# SCH_SPEAKER.net
KiCad netlist of a schematic drawn in Altium Designer
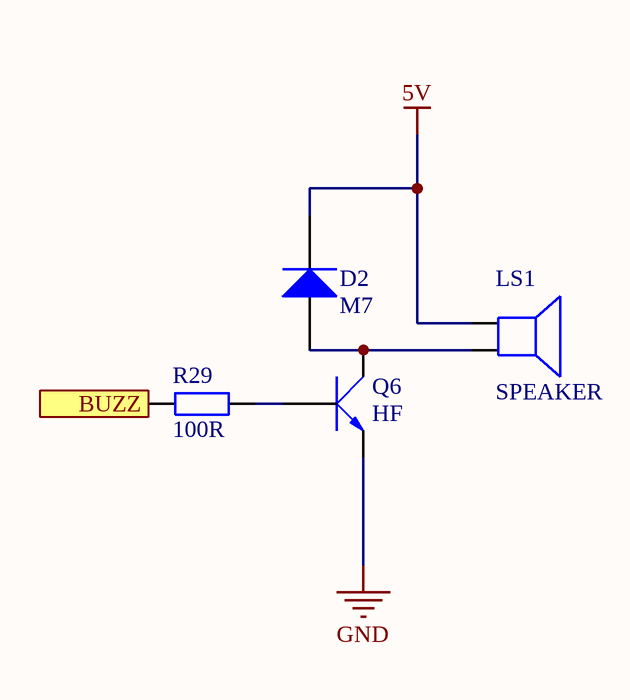
[diagram p0: SCH_SPEAKER.SchDoc]

(export (version "E")
  (design (tool "Eeschema 10.0.6"))
  (components
    (comp (ref "D2")
      (value "M7")
      (footprint "DIODE SMA")
      (description "Dán")
      (libsource (lib "Altium_Lib_by_KhueNguyenCreator") (part "Diode M7 ( 4007 )"))
    )
    (comp (ref "LS1")
      (value "SPEAKER")
      (footprint "Coi Chip Speacker")
      (description "Còi chip")
      (libsource (lib "Altium_Lib_by_KhueNguyenCreator") (part "Coi Chip Speaker"))
    )
    (comp (ref "Q6")
      (value "HF")
      (footprint "SOT23")
      (description "NPN transistor")
      (libsource (lib "Altium_Lib_by_KhueNguyenCreator") (part "C1815 HF SMD"))
    )
    (comp (ref "R29")
      (value "100R")
      (footprint "tro smd 0805")
      (description "Dán")
      (libsource (lib "Altium_Lib_by_KhueNguyenCreator") (part "Tro 0805 5% 100R"))
    )
  )
  (nets
    (net (code "2") (name "/BUZZ") (class "Default")
      (node (ref "R29") (pin "1") (pinfunction "1_1") (pintype "passive"))
    )
    (net (code "3") (name "5V") (class "Default")
      (node (ref "D2") (pin "2") (pinfunction "K_2") (pintype "passive"))
      (node (ref "LS1") (pin "1") (pinfunction "1_1") (pintype "passive"))
    )
    (net (code "4") (name "GND") (class "Default")
      (node (ref "Q6") (pin "2") (pinfunction "E_2") (pintype "passive"))
    )
    (net (code "5") (name "Net-(D2-A)") (class "Default")
      (node (ref "D2") (pin "1") (pinfunction "A_1") (pintype "passive"))
      (node (ref "LS1") (pin "2") (pinfunction "2_2") (pintype "passive"))
      (node (ref "Q6") (pin "3") (pinfunction "C_3") (pintype "passive"))
    )
    (net (code "6") (name "Net-(Q6-B)") (class "Default")
      (node (ref "Q6") (pin "1") (pinfunction "B_1") (pintype "passive"))
      (node (ref "R29") (pin "2") (pinfunction "2_2") (pintype "passive"))
    )
  )
)
